# Sheet1.net
KiCad netlist of a schematic drawn in Altium Designer
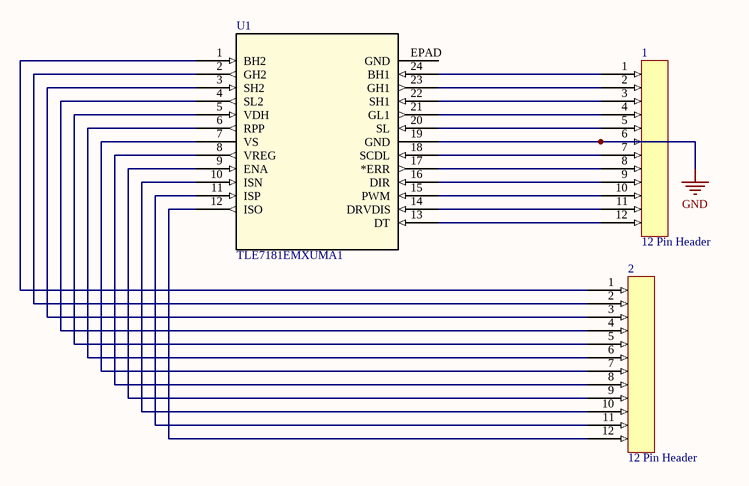
[diagram p0: Sheet1.SchDoc]

(export (version "E")
  (design (tool "Eeschema 10.0.6"))
  (components
    (comp (ref "1")
      (value "12 Pin Header")
      (footprint "12 Pin Header-Footprint-1")
      (libsource (lib "Esaias Ernfridsson") (part "New symbol 1"))
    )
    (comp (ref "2")
      (value "12 Pin Header")
      (footprint "12 Pin Header-Footprint-1")
      (libsource (lib "Esaias Ernfridsson") (part "New symbol 1"))
    )
    (comp (ref "U1")
      (value "TLE7181EMXUMA1")
      (footprint "PG-SSOP-4_INF")
      (fields (field (name "COPYRIGHT") "Copyright (C) 2026 Ultra Librarian. All rights reserved."))
      (libsource (lib "TLE7181EMXUMA1") (part "TLE7181EMXUMA1"))
    )
  )
  (nets
    (net (code "1") (name "GND") (class "Default")
      (node (ref "1") (pin "6") (pintype "input"))
      (node (ref "U1") (pin "19") (pinfunction "GND_19") (pintype "power_in"))
    )
    (net (code "2") (name "Net-(U1-*ERR)") (class "Default")
      (node (ref "1") (pin "8") (pintype "input"))
      (node (ref "U1") (pin "17") (pinfunction "*ERR_17") (pintype "output"))
    )
    (net (code "3") (name "Net-(U1-BH1)") (class "Default")
      (node (ref "1") (pin "1") (pintype "input"))
      (node (ref "U1") (pin "24") (pinfunction "BH1_24") (pintype "input"))
    )
    (net (code "4") (name "Net-(U1-BH2)") (class "Default")
      (node (ref "2") (pin "1") (pintype "input"))
      (node (ref "U1") (pin "1") (pinfunction "BH2_1") (pintype "input"))
    )
    (net (code "5") (name "Net-(U1-DIR)") (class "Default")
      (node (ref "1") (pin "9") (pintype "input"))
      (node (ref "U1") (pin "16") (pinfunction "DIR_16") (pintype "input"))
    )
    (net (code "6") (name "Net-(U1-DRVDIS)") (class "Default")
      (node (ref "1") (pin "11") (pintype "input"))
      (node (ref "U1") (pin "14") (pinfunction "DRVDIS_14") (pintype "input"))
    )
    (net (code "7") (name "Net-(U1-DT)") (class "Default")
      (node (ref "1") (pin "12") (pintype "input"))
      (node (ref "U1") (pin "13") (pinfunction "DT_13") (pintype "input"))
    )
    (net (code "8") (name "Net-(U1-ENA)") (class "Default")
      (node (ref "2") (pin "9") (pintype "input"))
      (node (ref "U1") (pin "9") (pinfunction "ENA_9") (pintype "input"))
    )
    (net (code "9") (name "Net-(U1-GH1)") (class "Default")
      (node (ref "1") (pin "2") (pintype "input"))
      (node (ref "U1") (pin "23") (pinfunction "GH1_23") (pintype "output"))
    )
    (net (code "10") (name "Net-(U1-GH2)") (class "Default")
      (node (ref "2") (pin "2") (pintype "input"))
      (node (ref "U1") (pin "2") (pinfunction "GH2_2") (pintype "output"))
    )
    (net (code "11") (name "Net-(U1-GL1)") (class "Default")
      (node (ref "1") (pin "4") (pintype "input"))
      (node (ref "U1") (pin "21") (pinfunction "GL1_21") (pintype "output"))
    )
    (net (code "12") (name "Net-(U1-ISN)") (class "Default")
      (node (ref "2") (pin "10") (pintype "input"))
      (node (ref "U1") (pin "10") (pinfunction "ISN_10") (pintype "input"))
    )
    (net (code "13") (name "Net-(U1-ISO)") (class "Default")
      (node (ref "2") (pin "12") (pintype "input"))
      (node (ref "U1") (pin "12") (pinfunction "ISO_12") (pintype "output"))
    )
    (net (code "14") (name "Net-(U1-ISP)") (class "Default")
      (node (ref "2") (pin "11") (pintype "input"))
      (node (ref "U1") (pin "11") (pinfunction "ISP_11") (pintype "input"))
    )
    (net (code "15") (name "Net-(U1-PWM)") (class "Default")
      (node (ref "1") (pin "10") (pintype "input"))
      (node (ref "U1") (pin "15") (pinfunction "PWM_15") (pintype "input"))
    )
    (net (code "16") (name "Net-(U1-RPP)") (class "Default")
      (node (ref "2") (pin "6") (pintype "input"))
      (node (ref "U1") (pin "6") (pinfunction "RPP_6") (pintype "output"))
    )
    (net (code "17") (name "Net-(U1-SCDL)") (class "Default")
      (node (ref "1") (pin "7") (pintype "input"))
      (node (ref "U1") (pin "18") (pinfunction "SCDL_18") (pintype "input"))
    )
    (net (code "18") (name "Net-(U1-SH1)") (class "Default")
      (node (ref "1") (pin "3") (pintype "input"))
      (node (ref "U1") (pin "22") (pinfunction "SH1_22") (pintype "input"))
    )
    (net (code "19") (name "Net-(U1-SH2)") (class "Default")
      (node (ref "2") (pin "3") (pintype "input"))
      (node (ref "U1") (pin "3") (pinfunction "SH2_3") (pintype "input"))
    )
    (net (code "20") (name "Net-(U1-SL)") (class "Default")
      (node (ref "1") (pin "5") (pintype "input"))
      (node (ref "U1") (pin "20") (pinfunction "SL_20") (pintype "input"))
    )
    (net (code "21") (name "Net-(U1-SL2)") (class "Default")
      (node (ref "2") (pin "4") (pintype "input"))
      (node (ref "U1") (pin "4") (pinfunction "SL2_4") (pintype "output"))
    )
    (net (code "22") (name "Net-(U1-VDH)") (class "Default")
      (node (ref "2") (pin "5") (pintype "input"))
      (node (ref "U1") (pin "5") (pinfunction "VDH_5") (pintype "input"))
    )
    (net (code "23") (name "Net-(U1-VREG)") (class "Default")
      (node (ref "2") (pin "8") (pintype "input"))
      (node (ref "U1") (pin "8") (pinfunction "VREG_8") (pintype "output"))
    )
    (net (code "24") (name "Net-(U1-VS)") (class "Default")
      (node (ref "2") (pin "7") (pintype "input"))
      (node (ref "U1") (pin "7") (pinfunction "VS_7") (pintype "power_in"))
    )
    (net (code "25") (name "unconnected-(U1-GND-PadEPAD)") (class "Default")
      (node (ref "U1") (pin "EPAD") (pinfunction "GND_EPAD") (pintype "power_in"))
    )
  )
)
